# d11toy4.net
KiCad netlist of a schematic drawn in EAGLE
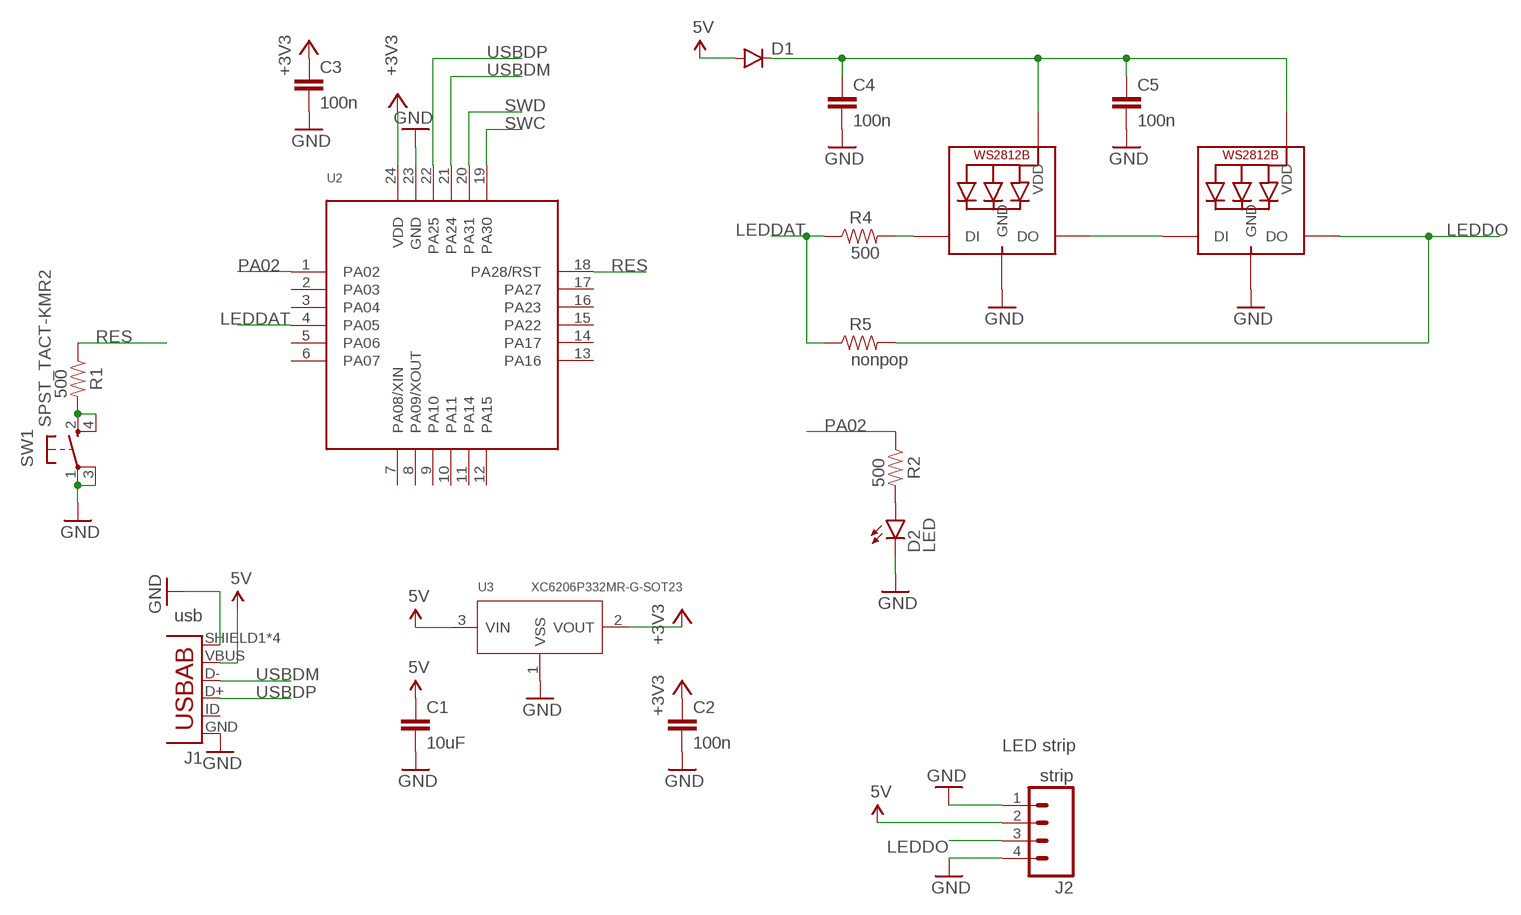
[diagram p0: schematic, sheet 1]

(export (version "E")
  (design (tool "Eeschema 10.0.6"))
  (components
    (comp (ref "C1")
      (value "10uF")
      (footprint "eagle-import:0603-CAP")
      (libsource (lib "eagle-import") (part "CAP0603-CAP"))
    )
    (comp (ref "C2")
      (value "100n")
      (footprint "eagle-import:0603-CAP")
      (libsource (lib "eagle-import") (part "CAP0603-CAP"))
    )
    (comp (ref "C3")
      (value "100n")
      (footprint "eagle-import:0603-CAP")
      (libsource (lib "eagle-import") (part "CAP0603-CAP"))
    )
    (comp (ref "C4")
      (value "100n")
      (footprint "eagle-import:0603-CAP")
      (libsource (lib "eagle-import") (part "CAP0603-CAP"))
    )
    (comp (ref "C5")
      (value "100n")
      (footprint "eagle-import:0603-CAP")
      (libsource (lib "eagle-import") (part "CAP0603-CAP"))
    )
    (comp (ref "D1")
      (value "DIODESOD523")
      (footprint "eagle-import:SOD523")
      (libsource (lib "eagle-import") (part "DIODESOD523"))
    )
    (comp (ref "D2")
      (value "LED")
      (footprint "eagle-import:LED-0603")
      (libsource (lib "eagle-import") (part "LED0603"))
    )
    (comp (ref "J1")
      (value "usb")
      (footprint "eagle-import:USB-AB-MICRO-SMD")
      (libsource (lib "eagle-import") (part "USB-AB"))
    )
    (comp (ref "J2")
      (value "strip")
      (footprint "eagle-import:1X04_NO_SILK_ALL_ROUND")
      (libsource (lib "eagle-import") (part "M04NO_SILK_ALL_ROUND"))
    )
    (comp (ref "LED1")
      (value "WS2812B5050")
      (footprint "eagle-import:WS2812B")
      (libsource (lib "eagle-import") (part "WS2812B5050"))
    )
    (comp (ref "LED2")
      (value "WS2812B5050")
      (footprint "eagle-import:WS2812B")
      (libsource (lib "eagle-import") (part "WS2812B5050"))
    )
    (comp (ref "R1")
      (value "500")
      (footprint "eagle-import:0603-RES")
      (libsource (lib "eagle-import") (part "RESISTOR0603-RES"))
    )
    (comp (ref "R2")
      (value "500")
      (footprint "eagle-import:0603-RES")
      (libsource (lib "eagle-import") (part "RESISTOR0603-RES"))
    )
    (comp (ref "R4")
      (value "500")
      (footprint "eagle-import:0603-RES")
      (libsource (lib "eagle-import") (part "RESISTOR0603-RES"))
    )
    (comp (ref "R5")
      (value "nonpop")
      (footprint "eagle-import:0603-RES")
      (libsource (lib "eagle-import") (part "RESISTOR0603-RES"))
    )
    (comp (ref "SW1")
      (value "SPST_TACT-KMR2")
      (footprint "eagle-import:KMR2")
      (libsource (lib "eagle-import") (part "SPST_TACT-KMR2"))
    )
    (comp (ref "U2")
      (value "SAMD11D14AM")
      (footprint "eagle-import:QFN24")
      (libsource (lib "eagle-import") (part "SAMD11D14AM"))
    )
    (comp (ref "U3")
      (value "XC6206P332MR-G-SOT23")
      (footprint "eagle-import:SOT-23")
      (fields (field (name "MPN") "XC6206P332MR-G"))
      (libsource (lib "eagle-import") (part "PMIC-LDO-XC6206P332MR-G(SOT23)"))
    )
  )
  (nets
    (net (code "1") (name "+3V3") (class "Default")
      (node (ref "C2") (pin "1") (pinfunction "1_1") (pintype "passive"))
      (node (ref "C3") (pin "1") (pinfunction "1_1") (pintype "passive"))
      (node (ref "U2") (pin "24") (pinfunction "VDD_24") (pintype "bidirectional"))
      (node (ref "U3") (pin "2") (pinfunction "VOUT_2") (pintype "output"))
    )
    (net (code "2") (name "/LEDDAT") (class "Default")
      (node (ref "R4") (pin "1") (pinfunction "1_1") (pintype "passive"))
      (node (ref "R5") (pin "1") (pinfunction "1_1") (pintype "passive"))
      (node (ref "U2") (pin "4") (pinfunction "PA05_4") (pintype "bidirectional"))
    )
    (net (code "3") (name "/LEDDO") (class "Default")
      (node (ref "J2") (pin "3") (pinfunction "3_3") (pintype "passive"))
      (node (ref "LED2") (pin "2-DOUT") (pinfunction "DO_2-DOUT") (pintype "output"))
      (node (ref "R5") (pin "2") (pinfunction "2_2") (pintype "passive"))
    )
    (net (code "4") (name "/PA02") (class "Default")
      (node (ref "R2") (pin "1") (pinfunction "1_1") (pintype "passive"))
      (node (ref "U2") (pin "1") (pinfunction "PA02_1") (pintype "bidirectional"))
    )
    (net (code "5") (name "/RES") (class "Default")
      (node (ref "R1") (pin "1") (pinfunction "1_1") (pintype "passive"))
      (node (ref "U2") (pin "18") (pinfunction "PA28/RST_18") (pintype "bidirectional"))
    )
    (net (code "6") (name "/SWC") (class "Default")
      (node (ref "U2") (pin "19") (pinfunction "PA30_19") (pintype "bidirectional"))
    )
    (net (code "7") (name "/SWD") (class "Default")
      (node (ref "U2") (pin "20") (pinfunction "PA31_20") (pintype "bidirectional"))
    )
    (net (code "8") (name "/USBDM") (class "Default")
      (node (ref "J1") (pin "D-") (pinfunction "D-_D-") (pintype "bidirectional"))
      (node (ref "U2") (pin "21") (pinfunction "PA24_21") (pintype "bidirectional"))
    )
    (net (code "9") (name "/USBDP") (class "Default")
      (node (ref "J1") (pin "D+") (pinfunction "D+_D+") (pintype "bidirectional"))
      (node (ref "U2") (pin "22") (pinfunction "PA25_22") (pintype "bidirectional"))
    )
    (net (code "10") (name "5V") (class "Default")
      (node (ref "C1") (pin "1") (pinfunction "1_1") (pintype "passive"))
      (node (ref "D1") (pin "A") (pinfunction "A_A") (pintype "passive"))
      (node (ref "J1") (pin "VBUS") (pinfunction "VBUS_VBUS") (pintype "bidirectional"))
      (node (ref "J2") (pin "2") (pinfunction "2_2") (pintype "passive"))
      (node (ref "U3") (pin "3") (pinfunction "VIN_3") (pintype "input"))
    )
    (net (code "11") (name "GND") (class "Default")
      (node (ref "C1") (pin "2") (pinfunction "2_2") (pintype "passive"))
      (node (ref "C2") (pin "2") (pinfunction "2_2") (pintype "passive"))
      (node (ref "C3") (pin "2") (pinfunction "2_2") (pintype "passive"))
      (node (ref "C4") (pin "2") (pinfunction "2_2") (pintype "passive"))
      (node (ref "C5") (pin "2") (pinfunction "2_2") (pintype "passive"))
      (node (ref "D2") (pin "C") (pinfunction "C_C") (pintype "passive"))
      (node (ref "J1") (pin "GND") (pinfunction "GND_GND") (pintype "bidirectional"))
      (node (ref "J1") (pin "SHIELD1") (pinfunction "SHIELD_SHIELD1") (pintype "bidirectional"))
      (node (ref "J1") (pin "SHIELD2") (pinfunction "SHIELD_SHIELD2") (pintype "bidirectional"))
      (node (ref "J1") (pin "SHIELD3") (pinfunction "SHIELD_SHIELD3") (pintype "bidirectional"))
      (node (ref "J1") (pin "SHIELD4") (pinfunction "SHIELD_SHIELD4") (pintype "bidirectional"))
      (node (ref "J2") (pin "1") (pinfunction "1_1") (pintype "passive"))
      (node (ref "J2") (pin "4") (pinfunction "4_4") (pintype "passive"))
      (node (ref "LED1") (pin "3-GND") (pinfunction "GND_3-GND") (pintype "power_in"))
      (node (ref "LED2") (pin "3-GND") (pinfunction "GND_3-GND") (pintype "power_in"))
      (node (ref "SW1") (pin "1") (pinfunction "P_1") (pintype "passive"))
      (node (ref "SW1") (pin "3") (pinfunction "P1_3") (pintype "passive"))
      (node (ref "U2") (pin "23") (pinfunction "GND_23") (pintype "bidirectional"))
      (node (ref "U3") (pin "1") (pinfunction "VSS_1") (pintype "power_in"))
    )
    (net (code "12") (name "Net-(D2-PadA)") (class "Default")
      (node (ref "D2") (pin "A") (pinfunction "A_A") (pintype "passive"))
      (node (ref "R2") (pin "2") (pinfunction "2_2") (pintype "passive"))
    )
    (net (code "13") (name "Net-(LED1-DI)") (class "Default")
      (node (ref "LED1") (pin "4-DIN") (pinfunction "DI_4-DIN") (pintype "input"))
      (node (ref "R4") (pin "2") (pinfunction "2_2") (pintype "passive"))
    )
    (net (code "14") (name "Net-(LED1-DO)") (class "Default")
      (node (ref "LED1") (pin "2-DOUT") (pinfunction "DO_2-DOUT") (pintype "output"))
      (node (ref "LED2") (pin "4-DIN") (pinfunction "DI_4-DIN") (pintype "input"))
    )
    (net (code "15") (name "Net-(LED1-VDD)") (class "Default")
      (node (ref "C4") (pin "1") (pinfunction "1_1") (pintype "passive"))
      (node (ref "C5") (pin "1") (pinfunction "1_1") (pintype "passive"))
      (node (ref "D1") (pin "C") (pinfunction "C_C") (pintype "passive"))
      (node (ref "LED1") (pin "1-VDD") (pinfunction "VDD_1-VDD") (pintype "power_in"))
      (node (ref "LED2") (pin "1-VDD") (pinfunction "VDD_1-VDD") (pintype "power_in"))
    )
    (net (code "16") (name "Net-(SW1-S)") (class "Default")
      (node (ref "R1") (pin "2") (pinfunction "2_2") (pintype "passive"))
      (node (ref "SW1") (pin "2") (pinfunction "S_2") (pintype "passive"))
      (node (ref "SW1") (pin "4") (pinfunction "S1_4") (pintype "passive"))
    )
    (net (code "17") (name "unconnected-(J1-USBID-PadID)") (class "Default")
      (node (ref "J1") (pin "ID") (pinfunction "USBID_ID") (pintype "bidirectional"))
    )
    (net (code "18") (name "unconnected-(U2-PA03-Pad2)") (class "Default")
      (node (ref "U2") (pin "2") (pinfunction "PA03_2") (pintype "bidirectional"))
    )
    (net (code "19") (name "unconnected-(U2-PA04-Pad3)") (class "Default")
      (node (ref "U2") (pin "3") (pinfunction "PA04_3") (pintype "bidirectional"))
    )
    (net (code "20") (name "unconnected-(U2-PA06-Pad5)") (class "Default")
      (node (ref "U2") (pin "5") (pinfunction "PA06_5") (pintype "bidirectional"))
    )
    (net (code "21") (name "unconnected-(U2-PA07-Pad6)") (class "Default")
      (node (ref "U2") (pin "6") (pinfunction "PA07_6") (pintype "bidirectional"))
    )
    (net (code "22") (name "unconnected-(U2-PA08{slash}XIN-Pad7)") (class "Default")
      (node (ref "U2") (pin "7") (pinfunction "PA08/XIN_7") (pintype "bidirectional"))
    )
    (net (code "23") (name "unconnected-(U2-PA09{slash}XOUT-Pad8)") (class "Default")
      (node (ref "U2") (pin "8") (pinfunction "PA09/XOUT_8") (pintype "bidirectional"))
    )
    (net (code "24") (name "unconnected-(U2-PA10-Pad9)") (class "Default")
      (node (ref "U2") (pin "9") (pinfunction "PA10_9") (pintype "bidirectional"))
    )
    (net (code "25") (name "unconnected-(U2-PA11-Pad10)") (class "Default")
      (node (ref "U2") (pin "10") (pinfunction "PA11_10") (pintype "bidirectional"))
    )
    (net (code "26") (name "unconnected-(U2-PA14-Pad11)") (class "Default")
      (node (ref "U2") (pin "11") (pinfunction "PA14_11") (pintype "bidirectional"))
    )
    (net (code "27") (name "unconnected-(U2-PA15-Pad12)") (class "Default")
      (node (ref "U2") (pin "12") (pinfunction "PA15_12") (pintype "bidirectional"))
    )
    (net (code "28") (name "unconnected-(U2-PA16-Pad13)") (class "Default")
      (node (ref "U2") (pin "13") (pinfunction "PA16_13") (pintype "bidirectional"))
    )
    (net (code "29") (name "unconnected-(U2-PA17-Pad14)") (class "Default")
      (node (ref "U2") (pin "14") (pinfunction "PA17_14") (pintype "bidirectional"))
    )
    (net (code "30") (name "unconnected-(U2-PA22-Pad15)") (class "Default")
      (node (ref "U2") (pin "15") (pinfunction "PA22_15") (pintype "bidirectional"))
    )
    (net (code "31") (name "unconnected-(U2-PA23-Pad16)") (class "Default")
      (node (ref "U2") (pin "16") (pinfunction "PA23_16") (pintype "bidirectional"))
    )
    (net (code "32") (name "unconnected-(U2-PA27-Pad17)") (class "Default")
      (node (ref "U2") (pin "17") (pinfunction "PA27_17") (pintype "bidirectional"))
    )
  )
)
